# AVR-Pocket-Programmer.net
KiCad netlist of a schematic drawn in EAGLE
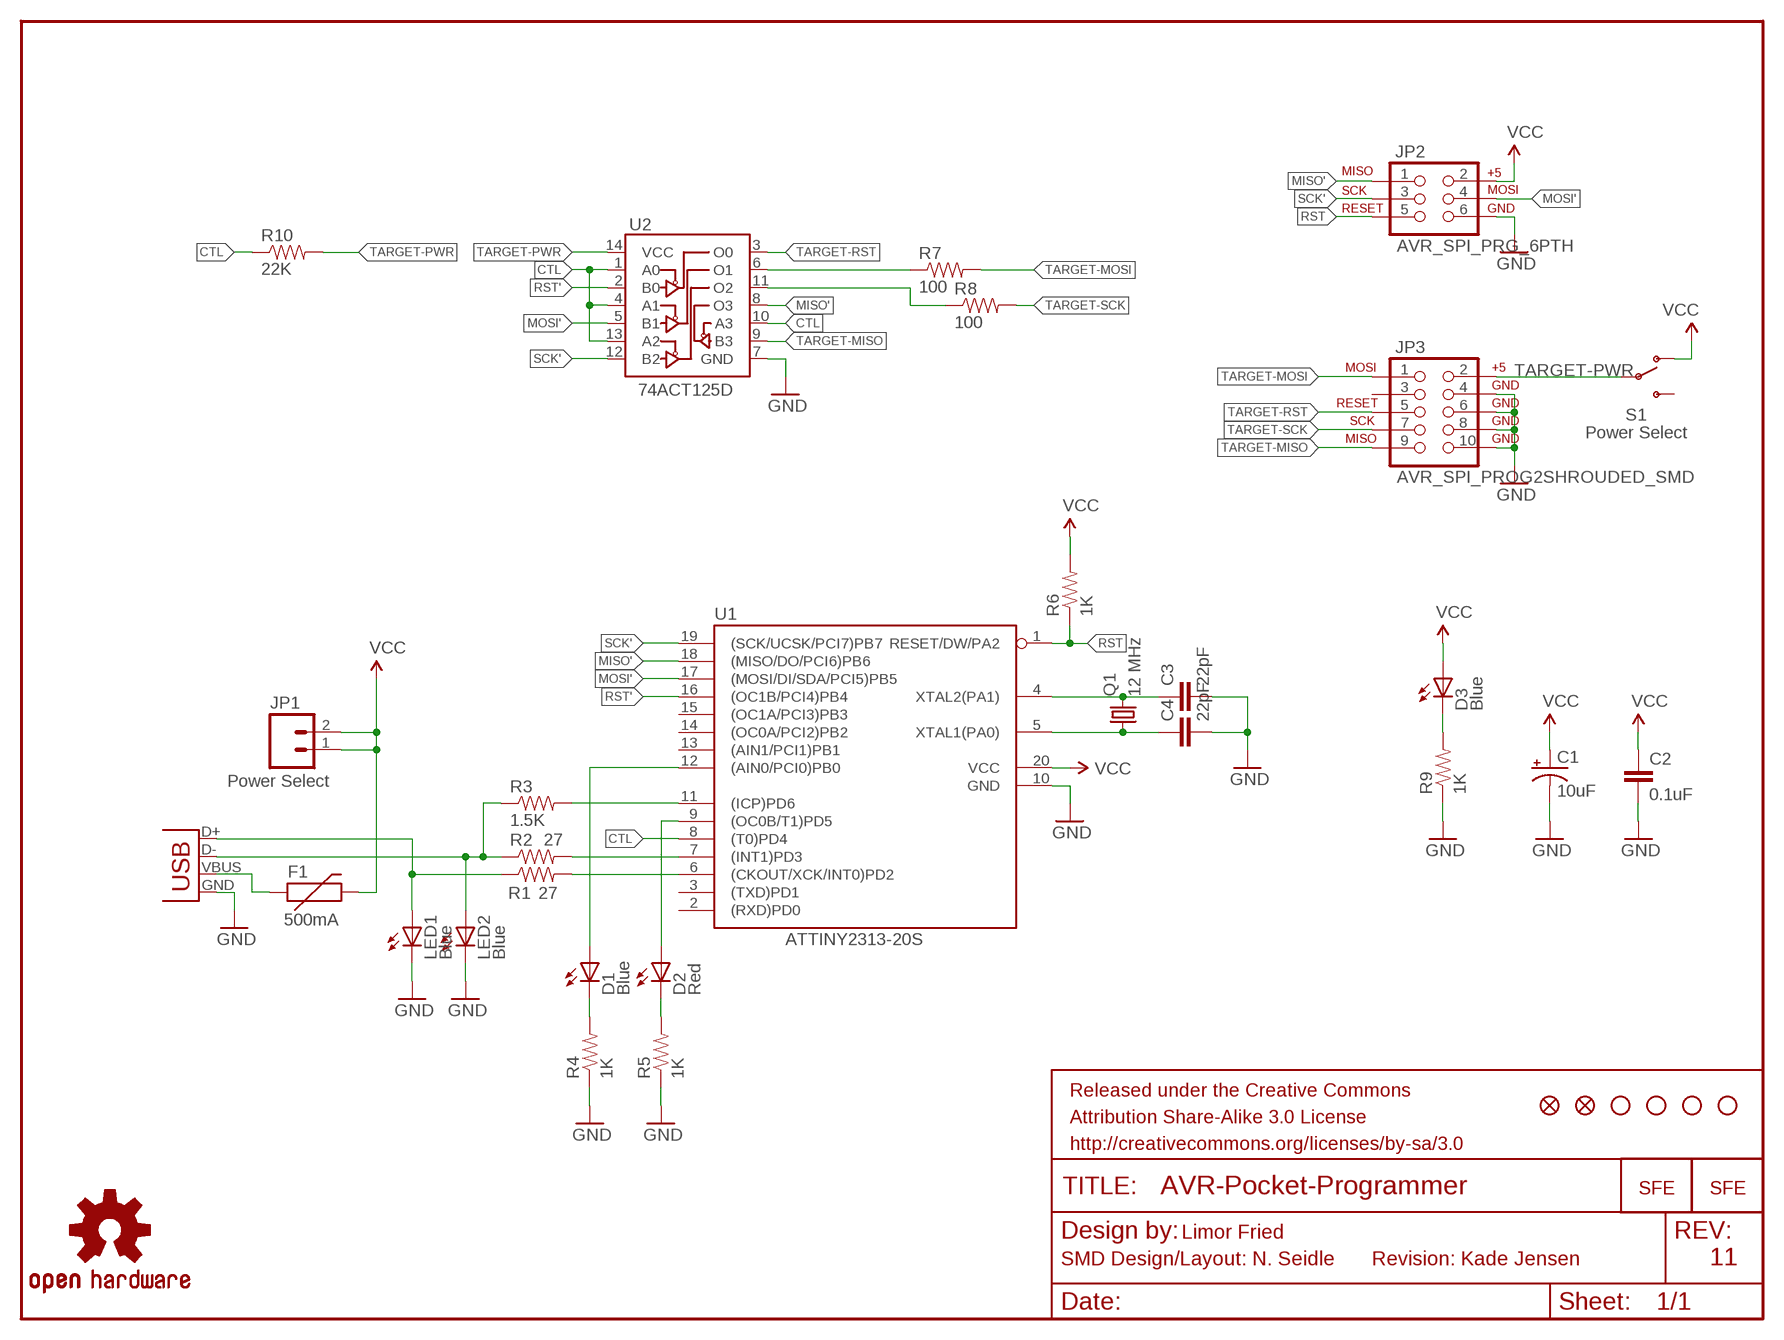
[diagram p0: schematic, sheet 1]

(export (version "E")
  (design (tool "Eeschema 10.0.6"))
  (components
    (comp (ref "C1")
      (value "10uF")
      (footprint "eagle-import:EIA3216")
      (libsource (lib "eagle-import") (part "CAP_POL1206"))
    )
    (comp (ref "C2")
      (value "0.1uF")
      (footprint "eagle-import:0603-CAP")
      (libsource (lib "eagle-import") (part "CAP0603-CAP"))
    )
    (comp (ref "C3")
      (value "22pF")
      (footprint "eagle-import:0603-CAP")
      (libsource (lib "eagle-import") (part "CAP0603-CAP"))
    )
    (comp (ref "C4")
      (value "22pF")
      (footprint "eagle-import:0603-CAP")
      (libsource (lib "eagle-import") (part "CAP0603-CAP"))
    )
    (comp (ref "D1")
      (value "Blue")
      (footprint "eagle-import:LED-0603")
      (libsource (lib "eagle-import") (part "LED0603"))
    )
    (comp (ref "D2")
      (value "Red")
      (footprint "eagle-import:LED-0603")
      (libsource (lib "eagle-import") (part "LED0603"))
    )
    (comp (ref "D3")
      (value "Blue")
      (footprint "eagle-import:LED-0603")
      (libsource (lib "eagle-import") (part "LED0603"))
    )
    (comp (ref "F1")
      (value "500mA")
      (footprint "eagle-import:PTC-1206-WIDE")
      (libsource (lib "eagle-import") (part "PTCSMD-W"))
    )
    (comp (ref "FRAME1")
      (value "FRAME-LETTER")
      (footprint "eagle-import:CREATIVE_COMMONS")
      (libsource (lib "eagle-import") (part "FRAME-LETTER"))
    )
    (comp (ref "JP1")
      (value "Power Select")
      (footprint "eagle-import:1X02")
      (libsource (lib "eagle-import") (part "M02PTH"))
    )
    (comp (ref "JP2")
      (value "AVR_SPI_PRG_6PTH")
      (footprint "eagle-import:2X3")
      (libsource (lib "eagle-import") (part "AVR_SPI_PRG_6PTH"))
    )
    (comp (ref "JP3")
      (value "AVR_SPI_PROG2SHROUDED_SMD")
      (footprint "eagle-import:2X5-SHROUDED_SMD")
      (libsource (lib "eagle-import") (part "AVR_SPI_PROG2SHROUDED_SMD"))
    )
    (comp (ref "LED1")
      (value "Blue")
      (footprint "eagle-import:LED-0603")
      (libsource (lib "eagle-import") (part "LED0603"))
    )
    (comp (ref "LED2")
      (value "Blue")
      (footprint "eagle-import:LED-0603")
      (libsource (lib "eagle-import") (part "LED0603"))
    )
    (comp (ref "LOGO1")
      (value "OSHW-LOGOM")
      (footprint "eagle-import:OSHW-LOGO-M")
      (libsource (lib "eagle-import") (part "OSHW-LOGOM"))
    )
    (comp (ref "Q1")
      (value "12 MHz")
      (footprint "eagle-import:CRYSTAL-SMD-5X3")
      (libsource (lib "eagle-import") (part "CRYSTAL5X3"))
    )
    (comp (ref "R1")
      (value "27")
      (footprint "eagle-import:0603-RES")
      (libsource (lib "eagle-import") (part "RESISTOR0603-RES"))
    )
    (comp (ref "R2")
      (value "27")
      (footprint "eagle-import:0603-RES")
      (libsource (lib "eagle-import") (part "RESISTOR0603-RES"))
    )
    (comp (ref "R3")
      (value "1.5K")
      (footprint "eagle-import:0603-RES")
      (libsource (lib "eagle-import") (part "RESISTOR0603-RES"))
    )
    (comp (ref "R4")
      (value "1K")
      (footprint "eagle-import:0603-RES")
      (libsource (lib "eagle-import") (part "RESISTOR0603-RES"))
    )
    (comp (ref "R5")
      (value "1K")
      (footprint "eagle-import:0603-RES")
      (libsource (lib "eagle-import") (part "RESISTOR0603-RES"))
    )
    (comp (ref "R6")
      (value "1K")
      (footprint "eagle-import:0603-RES")
      (libsource (lib "eagle-import") (part "RESISTOR0603-RES"))
    )
    (comp (ref "R7")
      (value "100")
      (footprint "eagle-import:0603-RES")
      (libsource (lib "eagle-import") (part "RESISTOR0603-RES"))
    )
    (comp (ref "R8")
      (value "100")
      (footprint "eagle-import:0603-RES")
      (libsource (lib "eagle-import") (part "RESISTOR0603-RES"))
    )
    (comp (ref "R9")
      (value "1K")
      (footprint "eagle-import:0603-RES")
      (libsource (lib "eagle-import") (part "RESISTOR0603-RES"))
    )
    (comp (ref "R10")
      (value "22K")
      (footprint "eagle-import:0603-RES")
      (libsource (lib "eagle-import") (part "RESISTOR0603-RES"))
    )
    (comp (ref "S1")
      (value "Power Select")
      (footprint "eagle-import:AYZ0202")
      (libsource (lib "eagle-import") (part "SWITCH-SPSTSMD"))
    )
    (comp (ref "U$1")
      (value "STAND-OFF")
      (footprint "eagle-import:STAND-OFF")
      (libsource (lib "eagle-import") (part "STAND-OFF"))
    )
    (comp (ref "U$2")
      (value "LOGO-SFESK")
      (footprint "eagle-import:SFE-LOGO-FLAME")
      (libsource (lib "eagle-import") (part "LOGO-SFESK"))
    )
    (comp (ref "U$3")
      (value "STAND-OFF")
      (footprint "eagle-import:STAND-OFF")
      (libsource (lib "eagle-import") (part "STAND-OFF"))
    )
    (comp (ref "U$4")
      (value "STAND-OFF")
      (footprint "eagle-import:STAND-OFF")
      (libsource (lib "eagle-import") (part "STAND-OFF"))
    )
    (comp (ref "U$5")
      (value "STAND-OFF")
      (footprint "eagle-import:STAND-OFF")
      (libsource (lib "eagle-import") (part "STAND-OFF"))
    )
    (comp (ref "U$6")
      (value "FIDUCIAL1X2")
      (footprint "eagle-import:FIDUCIAL-1X2")
      (libsource (lib "eagle-import") (part "FIDUCIAL1X2"))
    )
    (comp (ref "U$7")
      (value "FIDUCIAL1X2")
      (footprint "eagle-import:FIDUCIAL-1X2")
      (libsource (lib "eagle-import") (part "FIDUCIAL1X2"))
    )
    (comp (ref "U$8")
      (value "LOGO-SFENEW")
      (footprint "eagle-import:SFE-NEW-WEBLOGO")
      (libsource (lib "eagle-import") (part "LOGO-SFENEW"))
    )
    (comp (ref "U1")
      (value "ATTINY2313-20S")
      (footprint "eagle-import:SO20L")
      (libsource (lib "eagle-import") (part "ATTINY2313S-20"))
    )
    (comp (ref "U2")
      (value "74ACT125D")
      (footprint "eagle-import:SO014")
      (libsource (lib "eagle-import") (part "74ACT125D"))
    )
    (comp (ref "X2")
      (value "USBSMD")
      (footprint "eagle-import:USB-MINIB")
      (libsource (lib "eagle-import") (part "USBSMD"))
    )
  )
  (nets
    (net (code "1") (name "CTL") (class "Default")
      (node (ref "R10") (pin "1") (pinfunction "1_1") (pintype "passive"))
      (node (ref "U1") (pin "8") (pinfunction "(T0)PD4_8") (pintype "bidirectional"))
      (node (ref "U2") (pin "1") (pinfunction "A0_1") (pintype "bidirectional"))
      (node (ref "U2") (pin "10") (pinfunction "A3_10") (pintype "bidirectional"))
      (node (ref "U2") (pin "13") (pinfunction "A2_13") (pintype "bidirectional"))
      (node (ref "U2") (pin "4") (pinfunction "A1_4") (pintype "bidirectional"))
    )
    (net (code "2") (name "GND") (class "Default")
      (node (ref "C1") (pin "C") (pinfunction "-_C") (pintype "passive"))
      (node (ref "C2") (pin "2") (pinfunction "2_2") (pintype "passive"))
      (node (ref "C3") (pin "2") (pinfunction "2_2") (pintype "passive"))
      (node (ref "C4") (pin "2") (pinfunction "2_2") (pintype "passive"))
      (node (ref "JP2") (pin "6") (pinfunction "6_6") (pintype "passive"))
      (node (ref "JP3") (pin "10") (pinfunction "10_10") (pintype "passive"))
      (node (ref "JP3") (pin "4") (pinfunction "4_4") (pintype "passive"))
      (node (ref "JP3") (pin "6") (pinfunction "6_6") (pintype "passive"))
      (node (ref "JP3") (pin "8") (pinfunction "8_8") (pintype "passive"))
      (node (ref "LED1") (pin "C") (pinfunction "C_C") (pintype "passive"))
      (node (ref "LED2") (pin "C") (pinfunction "C_C") (pintype "passive"))
      (node (ref "R4") (pin "1") (pinfunction "1_1") (pintype "passive"))
      (node (ref "R5") (pin "1") (pinfunction "1_1") (pintype "passive"))
      (node (ref "R9") (pin "1") (pinfunction "1_1") (pintype "passive"))
      (node (ref "U1") (pin "10") (pinfunction "GND_10") (pintype "power_in"))
      (node (ref "U2") (pin "7") (pinfunction "GND_7") (pintype "bidirectional"))
      (node (ref "X2") (pin "GND") (pinfunction "GND_GND") (pintype "bidirectional"))
    )
    (net (code "3") (name "MISO'") (class "Default")
      (node (ref "JP2") (pin "1") (pinfunction "1_1") (pintype "passive"))
      (node (ref "U1") (pin "18") (pinfunction "(MISO/DO/PCI6)PB6_18") (pintype "bidirectional"))
      (node (ref "U2") (pin "8") (pinfunction "O3_8") (pintype "bidirectional"))
    )
    (net (code "4") (name "MOSI'") (class "Default")
      (node (ref "JP2") (pin "4") (pinfunction "4_4") (pintype "passive"))
      (node (ref "U1") (pin "17") (pinfunction "(MOSI/DI/SDA/PCI5)PB5_17") (pintype "bidirectional"))
      (node (ref "U2") (pin "5") (pinfunction "B1_5") (pintype "bidirectional"))
    )
    (net (code "5") (name "Net-(D1-PadC)") (class "Default")
      (node (ref "D1") (pin "C") (pinfunction "C_C") (pintype "passive"))
      (node (ref "R4") (pin "2") (pinfunction "2_2") (pintype "passive"))
    )
    (net (code "6") (name "Net-(D2-PadC)") (class "Default")
      (node (ref "D2") (pin "C") (pinfunction "C_C") (pintype "passive"))
      (node (ref "R5") (pin "2") (pinfunction "2_2") (pintype "passive"))
    )
    (net (code "7") (name "Net-(D3-PadC)") (class "Default")
      (node (ref "D3") (pin "C") (pinfunction "C_C") (pintype "passive"))
      (node (ref "R9") (pin "2") (pinfunction "2_2") (pintype "passive"))
    )
    (net (code "8") (name "Net-(F1-Pad1)") (class "Default")
      (node (ref "F1") (pin "1") (pinfunction "1_1") (pintype "bidirectional"))
      (node (ref "X2") (pin "VBUS") (pinfunction "VBUS_VBUS") (pintype "bidirectional"))
    )
    (net (code "9") (name "Net-(LED1-PadA)") (class "Default")
      (node (ref "LED1") (pin "A") (pinfunction "A_A") (pintype "passive"))
      (node (ref "R1") (pin "1") (pinfunction "1_1") (pintype "passive"))
      (node (ref "X2") (pin "D+") (pinfunction "D+_D+") (pintype "bidirectional"))
    )
    (net (code "10") (name "Net-(LED2-PadA)") (class "Default")
      (node (ref "LED2") (pin "A") (pinfunction "A_A") (pintype "passive"))
      (node (ref "R2") (pin "1") (pinfunction "1_1") (pintype "passive"))
      (node (ref "R3") (pin "1") (pinfunction "1_1") (pintype "passive"))
      (node (ref "X2") (pin "D-") (pinfunction "D-_D-") (pintype "bidirectional"))
    )
    (net (code "11") (name "Net-(Q1-2)") (class "Default")
      (node (ref "C3") (pin "1") (pinfunction "1_1") (pintype "passive"))
      (node (ref "Q1") (pin "3") (pinfunction "2_3") (pintype "passive"))
      (node (ref "U1") (pin "4") (pinfunction "XTAL2(PA1)_4") (pintype "bidirectional"))
    )
    (net (code "12") (name "Net-(U1-(AIN0{slash}PCI0)PB0)") (class "Default")
      (node (ref "D1") (pin "A") (pinfunction "A_A") (pintype "passive"))
      (node (ref "U1") (pin "12") (pinfunction "(AIN0/PCI0)PB0_12") (pintype "bidirectional"))
    )
    (net (code "13") (name "Net-(U1-(CKOUT{slash}XCK{slash}INT0)PD2)") (class "Default")
      (node (ref "R1") (pin "2") (pinfunction "2_2") (pintype "passive"))
      (node (ref "U1") (pin "6") (pinfunction "(CKOUT/XCK/INT0)PD2_6") (pintype "bidirectional"))
    )
    (net (code "14") (name "Net-(U1-(ICP)PD6)") (class "Default")
      (node (ref "R3") (pin "2") (pinfunction "2_2") (pintype "passive"))
      (node (ref "U1") (pin "11") (pinfunction "(ICP)PD6_11") (pintype "bidirectional"))
    )
    (net (code "15") (name "Net-(U1-(INT1)PD3)") (class "Default")
      (node (ref "R2") (pin "2") (pinfunction "2_2") (pintype "passive"))
      (node (ref "U1") (pin "7") (pinfunction "(INT1)PD3_7") (pintype "bidirectional"))
    )
    (net (code "16") (name "Net-(U1-(OC0B{slash}T1)PD5)") (class "Default")
      (node (ref "D2") (pin "A") (pinfunction "A_A") (pintype "passive"))
      (node (ref "U1") (pin "9") (pinfunction "(OC0B/T1)PD5_9") (pintype "bidirectional"))
    )
    (net (code "17") (name "Net-(U1-XTAL1(PA0))") (class "Default")
      (node (ref "C4") (pin "1") (pinfunction "1_1") (pintype "passive"))
      (node (ref "Q1") (pin "1") (pinfunction "1_1") (pintype "passive"))
      (node (ref "U1") (pin "5") (pinfunction "XTAL1(PA0)_5") (pintype "bidirectional"))
    )
    (net (code "18") (name "Net-(U2-O1)") (class "Default")
      (node (ref "R7") (pin "1") (pinfunction "1_1") (pintype "passive"))
      (node (ref "U2") (pin "6") (pinfunction "O1_6") (pintype "bidirectional"))
    )
    (net (code "19") (name "Net-(U2-O2)") (class "Default")
      (node (ref "R8") (pin "1") (pinfunction "1_1") (pintype "passive"))
      (node (ref "U2") (pin "11") (pinfunction "O2_11") (pintype "bidirectional"))
    )
    (net (code "20") (name "RST") (class "Default")
      (node (ref "JP2") (pin "5") (pinfunction "5_5") (pintype "passive"))
      (node (ref "R6") (pin "1") (pinfunction "1_1") (pintype "passive"))
      (node (ref "U1") (pin "1") (pinfunction "RESET/DW/PA2_1") (pintype "bidirectional"))
    )
    (net (code "21") (name "RST'") (class "Default")
      (node (ref "U1") (pin "16") (pinfunction "(OC1B/PCI4)PB4_16") (pintype "bidirectional"))
      (node (ref "U2") (pin "2") (pinfunction "B0_2") (pintype "bidirectional"))
    )
    (net (code "22") (name "SCK'") (class "Default")
      (node (ref "JP2") (pin "3") (pinfunction "3_3") (pintype "passive"))
      (node (ref "U1") (pin "19") (pinfunction "(SCK/UCSK/PCI7)PB7_19") (pintype "bidirectional"))
      (node (ref "U2") (pin "12") (pinfunction "B2_12") (pintype "bidirectional"))
    )
    (net (code "23") (name "TARGET-MISO") (class "Default")
      (node (ref "JP3") (pin "9") (pinfunction "9_9") (pintype "passive"))
      (node (ref "U2") (pin "9") (pinfunction "B3_9") (pintype "bidirectional"))
    )
    (net (code "24") (name "TARGET-MOSI") (class "Default")
      (node (ref "JP3") (pin "1") (pinfunction "1_1") (pintype "passive"))
      (node (ref "R7") (pin "2") (pinfunction "2_2") (pintype "passive"))
    )
    (net (code "25") (name "TARGET-PWR") (class "Default")
      (node (ref "JP3") (pin "2") (pinfunction "2_2") (pintype "passive"))
      (node (ref "R10") (pin "2") (pinfunction "2_2") (pintype "passive"))
      (node (ref "S1") (pin "2") (pinfunction "P_2") (pintype "passive"))
      (node (ref "U2") (pin "14") (pinfunction "VCC_14") (pintype "bidirectional"))
    )
    (net (code "26") (name "TARGET-RST") (class "Default")
      (node (ref "JP3") (pin "5") (pinfunction "5_5") (pintype "passive"))
      (node (ref "U2") (pin "3") (pinfunction "O0_3") (pintype "bidirectional"))
    )
    (net (code "27") (name "TARGET-SCK") (class "Default")
      (node (ref "JP3") (pin "7") (pinfunction "7_7") (pintype "passive"))
      (node (ref "R8") (pin "2") (pinfunction "2_2") (pintype "passive"))
    )
    (net (code "28") (name "VCC") (class "Default")
      (node (ref "C1") (pin "A") (pinfunction "+_A") (pintype "passive"))
      (node (ref "C2") (pin "1") (pinfunction "1_1") (pintype "passive"))
      (node (ref "D3") (pin "A") (pinfunction "A_A") (pintype "passive"))
      (node (ref "F1") (pin "2") (pinfunction "2_2") (pintype "bidirectional"))
      (node (ref "JP1") (pin "1") (pinfunction "1_1") (pintype "passive"))
      (node (ref "JP1") (pin "2") (pinfunction "2_2") (pintype "passive"))
      (node (ref "JP2") (pin "2") (pinfunction "2_2") (pintype "passive"))
      (node (ref "R6") (pin "2") (pinfunction "2_2") (pintype "passive"))
      (node (ref "S1") (pin "1") (pinfunction "O_1") (pintype "passive"))
      (node (ref "U1") (pin "20") (pinfunction "VCC_20") (pintype "power_in"))
    )
    (net (code "29") (name "unconnected-(JP3-Pad3)") (class "Default")
      (node (ref "JP3") (pin "3") (pinfunction "3_3") (pintype "passive"))
    )
    (net (code "30") (name "unconnected-(S1-S-Pad3)") (class "Default")
      (node (ref "S1") (pin "3") (pinfunction "S_3") (pintype "passive"))
    )
    (net (code "31") (name "unconnected-(U1-(AIN1{slash}PCI1)PB1-Pad13)") (class "Default")
      (node (ref "U1") (pin "13") (pinfunction "(AIN1/PCI1)PB1_13") (pintype "bidirectional"))
    )
    (net (code "32") (name "unconnected-(U1-(OC0A{slash}PCI2)PB2-Pad14)") (class "Default")
      (node (ref "U1") (pin "14") (pinfunction "(OC0A/PCI2)PB2_14") (pintype "bidirectional"))
    )
    (net (code "33") (name "unconnected-(U1-(OC1A{slash}PCI3)PB3-Pad15)") (class "Default")
      (node (ref "U1") (pin "15") (pinfunction "(OC1A/PCI3)PB3_15") (pintype "bidirectional"))
    )
    (net (code "34") (name "unconnected-(U1-(RXD)PD0-Pad2)") (class "Default")
      (node (ref "U1") (pin "2") (pinfunction "(RXD)PD0_2") (pintype "bidirectional"))
    )
    (net (code "35") (name "unconnected-(U1-(TXD)PD1-Pad3)") (class "Default")
      (node (ref "U1") (pin "3") (pinfunction "(TXD)PD1_3") (pintype "bidirectional"))
    )
  )
)
